# RadioPCB.net
KiCad netlist of a schematic drawn in Altium Designer
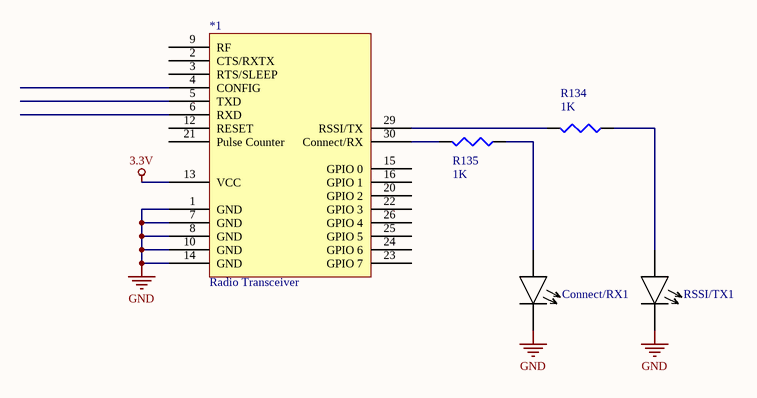
[diagram p0: RadioPCB.SchDoc]

(export (version "E")
  (design (tool "Eeschema 10.0.6"))
  (components
    (comp (ref "*1")
      (value "Radio Transceiver")
      (footprint "Radio Transiever")
      (libsource (lib "AvionicsParts") (part "Radio Transceiver"))
    )
    (comp (ref "Connect/RX1")
      (value "LED_B")
      (footprint "0402 footprint")
      (libsource (lib "AvionicsParts") (part "LED_B"))
    )
    (comp (ref "R134")
      (value "1K")
      (description "Resistor")
      (fields (field (name "Comment") "Res3") (field (name "PUBLISHER") "Altium Limited"))
      (libsource (lib "Miscellaneous Devices") (part "Res3"))
    )
    (comp (ref "R135")
      (value "1K")
      (description "Resistor")
      (fields (field (name "Comment") "Res3") (field (name "PUBLISHER") "Altium Limited"))
      (libsource (lib "Miscellaneous Devices") (part "Res3"))
    )
    (comp (ref "RSSI/TX1")
      (value "LED_B")
      (footprint "0402 footprint")
      (libsource (lib "AvionicsParts") (part "LED_B"))
    )
  )
  (nets
    (net (code "1") (name "3.3V") (class "Default")
      (node (ref "*1") (pin "13") (pinfunction "VCC_13") (pintype "passive"))
    )
    (net (code "2") (name "GND") (class "Default")
      (node (ref "*1") (pin "1") (pinfunction "GND_1") (pintype "passive"))
      (node (ref "*1") (pin "10") (pinfunction "GND_10") (pintype "passive"))
      (node (ref "*1") (pin "14") (pinfunction "GND_14") (pintype "passive"))
      (node (ref "*1") (pin "7") (pinfunction "GND_7") (pintype "passive"))
      (node (ref "*1") (pin "8") (pinfunction "GND_8") (pintype "passive"))
      (node (ref "Connect/RX1") (pin "2") (pinfunction "2_2") (pintype "passive"))
      (node (ref "RSSI/TX1") (pin "2") (pinfunction "2_2") (pintype "passive"))
    )
    (net (code "3") (name "Net-(*1-Connect{slash}RX)") (class "Default")
      (node (ref "*1") (pin "30") (pinfunction "Connect/RX_30") (pintype "passive"))
      (node (ref "R135") (pin "2") (pinfunction "2_2") (pintype "passive"))
    )
    (net (code "4") (name "Net-(*1-RSSI{slash}TX)") (class "Default")
      (node (ref "*1") (pin "29") (pinfunction "RSSI/TX_29") (pintype "passive"))
      (node (ref "R134") (pin "2") (pinfunction "2_2") (pintype "passive"))
    )
    (net (code "5") (name "Net-(Connect/RX1-Pad1)") (class "Default")
      (node (ref "Connect/RX1") (pin "1") (pinfunction "1_1") (pintype "passive"))
      (node (ref "R135") (pin "1") (pinfunction "1_1") (pintype "passive"))
    )
    (net (code "6") (name "Net-(R134-Pad1)") (class "Default")
      (node (ref "R134") (pin "1") (pinfunction "1_1") (pintype "passive"))
      (node (ref "RSSI/TX1") (pin "1") (pinfunction "1_1") (pintype "passive"))
    )
    (net (code "7") (name "unconnected-(*1-CONFIG-Pad4)") (class "Default")
      (node (ref "*1") (pin "4") (pinfunction "CONFIG_4") (pintype "passive"))
    )
    (net (code "8") (name "unconnected-(*1-CTS{slash}RXTX-Pad2)") (class "Default")
      (node (ref "*1") (pin "2") (pinfunction "CTS/RXTX_2") (pintype "passive"))
    )
    (net (code "9") (name "unconnected-(*1-GPIO_0-Pad15)") (class "Default")
      (node (ref "*1") (pin "15") (pinfunction "GPIO_0_15") (pintype "passive"))
    )
    (net (code "10") (name "unconnected-(*1-GPIO_1-Pad16)") (class "Default")
      (node (ref "*1") (pin "16") (pinfunction "GPIO_1_16") (pintype "passive"))
    )
    (net (code "11") (name "unconnected-(*1-GPIO_2-Pad20)") (class "Default")
      (node (ref "*1") (pin "20") (pinfunction "GPIO_2_20") (pintype "passive"))
    )
    (net (code "12") (name "unconnected-(*1-GPIO_3-Pad22)") (class "Default")
      (node (ref "*1") (pin "22") (pinfunction "GPIO_3_22") (pintype "passive"))
    )
    (net (code "13") (name "unconnected-(*1-GPIO_4-Pad26)") (class "Default")
      (node (ref "*1") (pin "26") (pinfunction "GPIO_4_26") (pintype "passive"))
    )
    (net (code "14") (name "unconnected-(*1-GPIO_5-Pad25)") (class "Default")
      (node (ref "*1") (pin "25") (pinfunction "GPIO_5_25") (pintype "passive"))
    )
    (net (code "15") (name "unconnected-(*1-GPIO_6-Pad24)") (class "Default")
      (node (ref "*1") (pin "24") (pinfunction "GPIO_6_24") (pintype "passive"))
    )
    (net (code "16") (name "unconnected-(*1-GPIO_7-Pad23)") (class "Default")
      (node (ref "*1") (pin "23") (pinfunction "GPIO_7_23") (pintype "passive"))
    )
    (net (code "17") (name "unconnected-(*1-Pulse_Counter-Pad21)") (class "Default")
      (node (ref "*1") (pin "21") (pinfunction "Pulse_Counter_21") (pintype "passive"))
    )
    (net (code "18") (name "unconnected-(*1-RESET-Pad12)") (class "Default")
      (node (ref "*1") (pin "12") (pinfunction "RESET_12") (pintype "passive"))
    )
    (net (code "19") (name "unconnected-(*1-RF-Pad9)") (class "Default")
      (node (ref "*1") (pin "9") (pinfunction "RF_9") (pintype "passive"))
    )
    (net (code "20") (name "unconnected-(*1-RTS{slash}SLEEP-Pad3)") (class "Default")
      (node (ref "*1") (pin "3") (pinfunction "RTS/SLEEP_3") (pintype "passive"))
    )
    (net (code "21") (name "unconnected-(*1-RXD-Pad6)") (class "Default")
      (node (ref "*1") (pin "6") (pinfunction "RXD_6") (pintype "passive"))
    )
    (net (code "22") (name "unconnected-(*1-TXD-Pad5)") (class "Default")
      (node (ref "*1") (pin "5") (pinfunction "TXD_5") (pintype "passive"))
    )
  )
)
